# IDP5.net
KiCad netlist of a schematic drawn in EAGLE
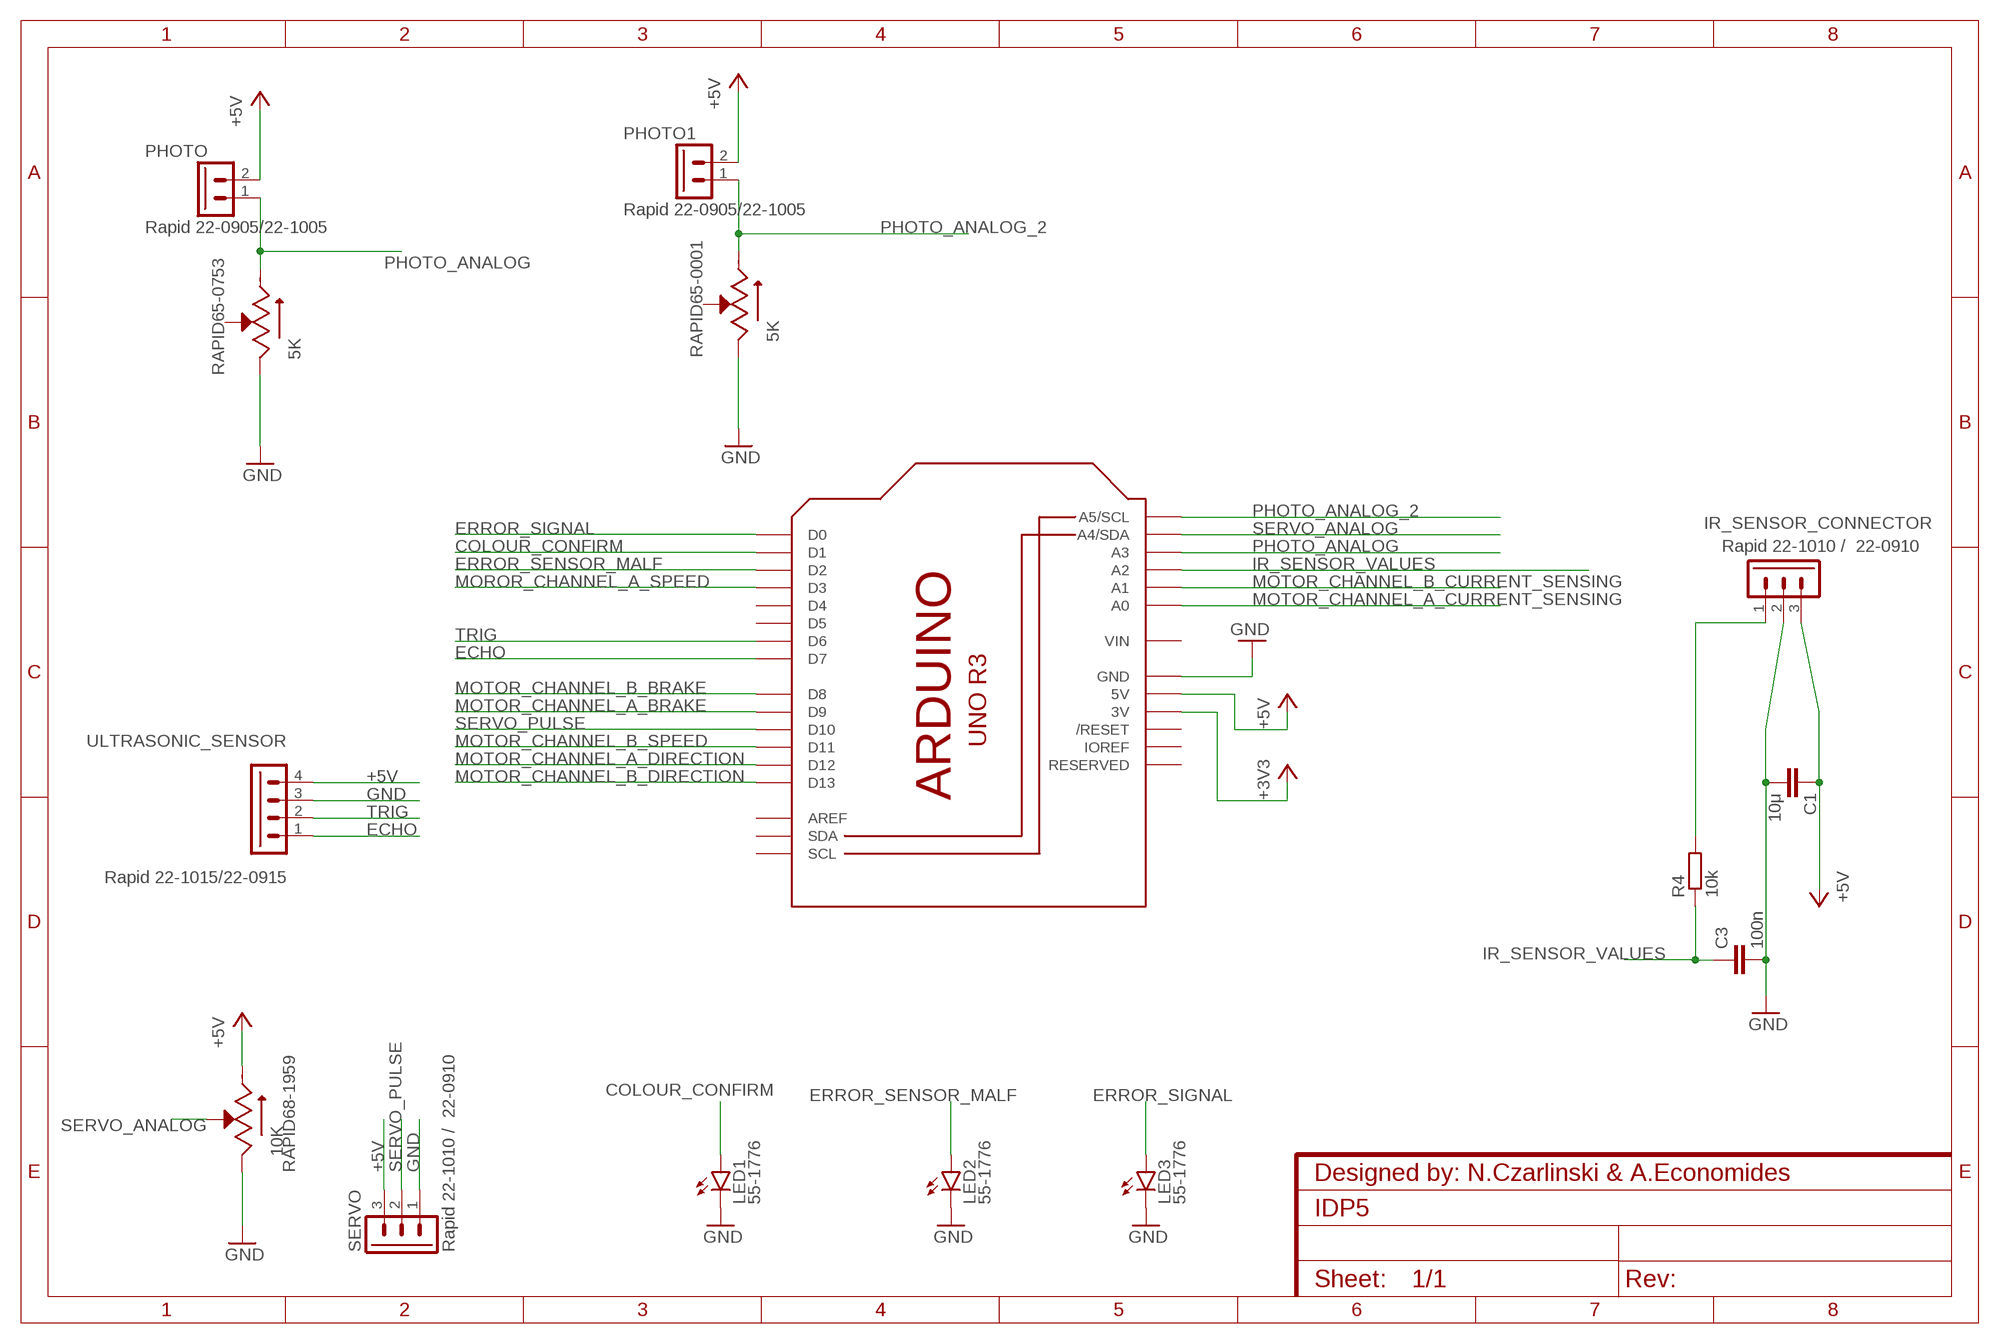
[diagram p0: schematic, sheet 1]

(export (version "E")
  (design (tool "Eeschema 10.0.6"))
  (components
    (comp (ref "C1")
      (value "10μ")
      (footprint "eagle-import:C025-024X044")
      (libsource (lib "eagle-import") (part "C-EU025-024X044"))
    )
    (comp (ref "C3")
      (value "100n")
      (footprint "eagle-import:C025-024X044")
      (libsource (lib "eagle-import") (part "C-EU025-024X044"))
    )
    (comp (ref "IR_SENSOR_CONNECTOR")
      (value "Rapid 22-1010 / 22-0910")
      (footprint "eagle-import:7395-03")
      (fields (field (name "MF") "MOLEX"))
      (libsource (lib "eagle-import") (part "22-?-0305-7038"))
    )
    (comp (ref "LED1")
      (value "55-1776")
      (footprint "eagle-import:LED3MM")
      (libsource (lib "eagle-import") (part "LED_23MM"))
    )
    (comp (ref "LED2")
      (value "55-1776")
      (footprint "eagle-import:LED3MM")
      (libsource (lib "eagle-import") (part "LED_23MM"))
    )
    (comp (ref "LED3")
      (value "55-1776")
      (footprint "eagle-import:LED3MM")
      (libsource (lib "eagle-import") (part "LED_23MM"))
    )
    (comp (ref "M1")
      (value "IDP_PROTOBOARD")
      (footprint "eagle-import:IDP_PROTO")
      (libsource (lib "eagle-import") (part "IDP_PROTOBOARD"))
    )
    (comp (ref "PHOTO")
      (value "Rapid 22-0905/22-1005")
      (footprint "eagle-import:7395-02")
      (fields (field (name "MF") "MOLEX"))
      (libsource (lib "eagle-import") (part "22-?-0205-7028"))
    )
    (comp (ref "PHOTO1")
      (value "Rapid 22-0905/22-1005")
      (footprint "eagle-import:7395-02")
      (fields (field (name "MF") "MOLEX"))
      (libsource (lib "eagle-import") (part "22-?-0205-7028"))
    )
    (comp (ref "R4")
      (value "10k")
      (footprint "eagle-import:0204_7")
      (libsource (lib "eagle-import") (part "R-EU_0204/7"))
    )
    (comp (ref "RAPID65-0001")
      (value "5K")
      (footprint "eagle-import:TRIM_3296W-1-250")
      (fields (field (name "MF") "Bourns") (field (name "MP") "3296W-1-250"))
      (libsource (lib "eagle-import") (part "POT"))
    )
    (comp (ref "RAPID65-0753")
      (value "5K")
      (footprint "eagle-import:TRIM_3296W-1-250")
      (fields (field (name "MF") "Bourns") (field (name "MP") "3296W-1-250"))
      (libsource (lib "eagle-import") (part "POT"))
    )
    (comp (ref "RAPID68-1959")
      (value "10K")
      (footprint "eagle-import:TRIM_3296W-1-250")
      (fields (field (name "MF") "Bourns") (field (name "MP") "3296W-1-250"))
      (libsource (lib "eagle-import") (part "POT"))
    )
    (comp (ref "SERVO")
      (value "Rapid 22-1010 / 22-0910")
      (footprint "eagle-import:7395-03")
      (fields (field (name "MF") "MOLEX"))
      (libsource (lib "eagle-import") (part "22-?-0305-7038"))
    )
    (comp (ref "ULTRASONIC_SENSOR")
      (value "Rapid 22-1015/22-0915")
      (footprint "eagle-import:7395-04")
      (fields (field (name "MF") "MOLEX"))
      (libsource (lib "eagle-import") (part "22-?-0405-7048"))
    )
  )
  (nets
    (net (code "1") (name "+3V3") (class "Default")
      (node (ref "M1") (pin "3V") (pinfunction "3V_3V") (pintype "power_in"))
    )
    (net (code "2") (name "+5V") (class "Default")
      (node (ref "C1") (pin "1") (pinfunction "1_1") (pintype "passive"))
      (node (ref "IR_SENSOR_CONNECTOR") (pin "3") (pinfunction "3_3") (pintype "passive"))
      (node (ref "M1") (pin "5V") (pinfunction "5V_5V") (pintype "power_in"))
      (node (ref "M1") (pin "5V@0") (pinfunction "5V_5V@0") (pintype "power_in"))
      (node (ref "M1") (pin "5V@1") (pinfunction "5V_5V@1") (pintype "power_in"))
      (node (ref "M1") (pin "5V@10") (pinfunction "5V_5V@10") (pintype "power_in"))
      (node (ref "M1") (pin "5V@11") (pinfunction "5V_5V@11") (pintype "power_in"))
      (node (ref "M1") (pin "5V@12") (pinfunction "5V_5V@12") (pintype "power_in"))
      (node (ref "M1") (pin "5V@13") (pinfunction "5V_5V@13") (pintype "power_in"))
      (node (ref "M1") (pin "5V@14") (pinfunction "5V_5V@14") (pintype "power_in"))
      (node (ref "M1") (pin "5V@15") (pinfunction "5V_5V@15") (pintype "power_in"))
      (node (ref "M1") (pin "5V@16") (pinfunction "5V_5V@16") (pintype "power_in"))
      (node (ref "M1") (pin "5V@17") (pinfunction "5V_5V@17") (pintype "power_in"))
      (node (ref "M1") (pin "5V@18") (pinfunction "5V_5V@18") (pintype "power_in"))
      (node (ref "M1") (pin "5V@19") (pinfunction "5V_5V@19") (pintype "power_in"))
      (node (ref "M1") (pin "5V@2") (pinfunction "5V_5V@2") (pintype "power_in"))
      (node (ref "M1") (pin "5V@20") (pinfunction "5V_5V@20") (pintype "power_in"))
      (node (ref "M1") (pin "5V@21") (pinfunction "5V_5V@21") (pintype "power_in"))
      (node (ref "M1") (pin "5V@22") (pinfunction "5V_5V@22") (pintype "power_in"))
      (node (ref "M1") (pin "5V@23") (pinfunction "5V_5V@23") (pintype "power_in"))
      (node (ref "M1") (pin "5V@24") (pinfunction "5V_5V@24") (pintype "power_in"))
      (node (ref "M1") (pin "5V@25") (pinfunction "5V_5V@25") (pintype "power_in"))
      (node (ref "M1") (pin "5V@26") (pinfunction "5V_5V@26") (pintype "power_in"))
      (node (ref "M1") (pin "5V@27") (pinfunction "5V_5V@27") (pintype "power_in"))
      (node (ref "M1") (pin "5V@28") (pinfunction "5V_5V@28") (pintype "power_in"))
      (node (ref "M1") (pin "5V@29") (pinfunction "5V_5V@29") (pintype "power_in"))
      (node (ref "M1") (pin "5V@3") (pinfunction "5V_5V@3") (pintype "power_in"))
      (node (ref "M1") (pin "5V@30") (pinfunction "5V_5V@30") (pintype "power_in"))
      (node (ref "M1") (pin "5V@31") (pinfunction "5V_5V@31") (pintype "power_in"))
      (node (ref "M1") (pin "5V@32") (pinfunction "5V_5V@32") (pintype "power_in"))
      (node (ref "M1") (pin "5V@33") (pinfunction "5V_5V@33") (pintype "power_in"))
      (node (ref "M1") (pin "5V@34") (pinfunction "5V_5V@34") (pintype "power_in"))
      (node (ref "M1") (pin "5V@35") (pinfunction "5V_5V@35") (pintype "power_in"))
      (node (ref "M1") (pin "5V@36") (pinfunction "5V_5V@36") (pintype "power_in"))
      (node (ref "M1") (pin "5V@37") (pinfunction "5V_5V@37") (pintype "power_in"))
      (node (ref "M1") (pin "5V@38") (pinfunction "5V_5V@38") (pintype "power_in"))
      (node (ref "M1") (pin "5V@39") (pinfunction "5V_5V@39") (pintype "power_in"))
      (node (ref "M1") (pin "5V@4") (pinfunction "5V_5V@4") (pintype "power_in"))
      (node (ref "M1") (pin "5V@40") (pinfunction "5V_5V@40") (pintype "power_in"))
      (node (ref "M1") (pin "5V@5") (pinfunction "5V_5V@5") (pintype "power_in"))
      (node (ref "M1") (pin "5V@6") (pinfunction "5V_5V@6") (pintype "power_in"))
      (node (ref "M1") (pin "5V@7") (pinfunction "5V_5V@7") (pintype "power_in"))
      (node (ref "M1") (pin "5V@8") (pinfunction "5V_5V@8") (pintype "power_in"))
      (node (ref "M1") (pin "5V@9") (pinfunction "5V_5V@9") (pintype "power_in"))
      (node (ref "PHOTO") (pin "2") (pinfunction "2_2") (pintype "passive"))
      (node (ref "PHOTO1") (pin "2") (pinfunction "2_2") (pintype "passive"))
      (node (ref "RAPID68-1959") (pin "3") (pinfunction "CW_3") (pintype "passive"))
      (node (ref "SERVO") (pin "3") (pinfunction "3_3") (pintype "passive"))
      (node (ref "ULTRASONIC_SENSOR") (pin "4") (pinfunction "4_4") (pintype "passive"))
    )
    (net (code "3") (name "/COLOUR_CONFIRM") (class "Default")
      (node (ref "LED1") (pin "A") (pinfunction "A_A") (pintype "passive"))
      (node (ref "M1") (pin "D1") (pinfunction "D1_D1") (pintype "bidirectional"))
    )
    (net (code "4") (name "/ECHO") (class "Default")
      (node (ref "M1") (pin "D7") (pinfunction "D7_D7") (pintype "bidirectional"))
      (node (ref "ULTRASONIC_SENSOR") (pin "1") (pinfunction "1_1") (pintype "passive"))
    )
    (net (code "5") (name "/ERROR_SENSOR_MALF") (class "Default")
      (node (ref "LED2") (pin "A") (pinfunction "A_A") (pintype "passive"))
      (node (ref "M1") (pin "D2") (pinfunction "D2_D2") (pintype "bidirectional"))
    )
    (net (code "6") (name "/ERROR_SIGNAL") (class "Default")
      (node (ref "LED3") (pin "A") (pinfunction "A_A") (pintype "passive"))
      (node (ref "M1") (pin "D0") (pinfunction "D0_D0") (pintype "bidirectional"))
    )
    (net (code "7") (name "/IR_SENSOR_VALUES") (class "Default")
      (node (ref "C3") (pin "1") (pinfunction "1_1") (pintype "passive"))
      (node (ref "M1") (pin "A2") (pinfunction "A2_A2") (pintype "bidirectional"))
      (node (ref "R4") (pin "1") (pinfunction "1_1") (pintype "passive"))
    )
    (net (code "8") (name "/MOROR_CHANNEL_A_SPEED") (class "Default")
      (node (ref "M1") (pin "D3") (pinfunction "D3_D3") (pintype "bidirectional"))
    )
    (net (code "9") (name "/MOTOR_CHANNEL_A_BRAKE") (class "Default")
      (node (ref "M1") (pin "D9") (pinfunction "D9_D9") (pintype "bidirectional"))
    )
    (net (code "10") (name "/MOTOR_CHANNEL_A_CURRENT_SENSING") (class "Default")
      (node (ref "M1") (pin "A0") (pinfunction "A0_A0") (pintype "bidirectional"))
    )
    (net (code "11") (name "/MOTOR_CHANNEL_A_DIRECTION") (class "Default")
      (node (ref "M1") (pin "D12") (pinfunction "D12_D12") (pintype "bidirectional"))
    )
    (net (code "12") (name "/MOTOR_CHANNEL_B_BRAKE") (class "Default")
      (node (ref "M1") (pin "D8") (pinfunction "D8_D8") (pintype "bidirectional"))
    )
    (net (code "13") (name "/MOTOR_CHANNEL_B_CURRENT_SENSING") (class "Default")
      (node (ref "M1") (pin "A1") (pinfunction "A1_A1") (pintype "bidirectional"))
    )
    (net (code "14") (name "/MOTOR_CHANNEL_B_DIRECTION") (class "Default")
      (node (ref "M1") (pin "D13") (pinfunction "D13_D13") (pintype "bidirectional"))
    )
    (net (code "15") (name "/MOTOR_CHANNEL_B_SPEED") (class "Default")
      (node (ref "M1") (pin "D11") (pinfunction "D11_D11") (pintype "bidirectional"))
    )
    (net (code "16") (name "/PHOTO_ANALOG") (class "Default")
      (node (ref "M1") (pin "A3") (pinfunction "A3_A3") (pintype "bidirectional"))
      (node (ref "PHOTO") (pin "1") (pinfunction "1_1") (pintype "passive"))
      (node (ref "RAPID65-0753") (pin "3") (pinfunction "CW_3") (pintype "passive"))
    )
    (net (code "17") (name "/PHOTO_ANALOG_2") (class "Default")
      (node (ref "M1") (pin "A5") (pinfunction "A5/SCL_A5") (pintype "bidirectional"))
      (node (ref "PHOTO1") (pin "1") (pinfunction "1_1") (pintype "passive"))
      (node (ref "RAPID65-0001") (pin "3") (pinfunction "CW_3") (pintype "passive"))
    )
    (net (code "18") (name "/SERVO_ANALOG") (class "Default")
      (node (ref "M1") (pin "A4") (pinfunction "A4/SDA_A4") (pintype "bidirectional"))
      (node (ref "RAPID68-1959") (pin "2") (pinfunction "WIPER_2") (pintype "passive"))
    )
    (net (code "19") (name "/SERVO_PULSE") (class "Default")
      (node (ref "M1") (pin "D10") (pinfunction "D10_D10") (pintype "bidirectional"))
      (node (ref "SERVO") (pin "2") (pinfunction "2_2") (pintype "passive"))
    )
    (net (code "20") (name "/TRIG") (class "Default")
      (node (ref "M1") (pin "D6") (pinfunction "D6_D6") (pintype "bidirectional"))
      (node (ref "ULTRASONIC_SENSOR") (pin "2") (pinfunction "2_2") (pintype "passive"))
    )
    (net (code "21") (name "GND") (class "Default")
      (node (ref "C1") (pin "2") (pinfunction "2_2") (pintype "passive"))
      (node (ref "C3") (pin "2") (pinfunction "2_2") (pintype "passive"))
      (node (ref "IR_SENSOR_CONNECTOR") (pin "2") (pinfunction "2_2") (pintype "passive"))
      (node (ref "LED1") (pin "K") (pinfunction "C_K") (pintype "passive"))
      (node (ref "LED2") (pin "K") (pinfunction "C_K") (pintype "passive"))
      (node (ref "LED3") (pin "K") (pinfunction "C_K") (pintype "passive"))
      (node (ref "M1") (pin "GND") (pinfunction "GND_GND") (pintype "power_in"))
      (node (ref "M1") (pin "GND16") (pinfunction "GND_GND16") (pintype "power_in"))
      (node (ref "M1") (pin "GND17") (pinfunction "GND_GND17") (pintype "power_in"))
      (node (ref "M1") (pin "GND18") (pinfunction "GND_GND18") (pintype "power_in"))
      (node (ref "M1") (pin "GND19") (pinfunction "GND_GND19") (pintype "power_in"))
      (node (ref "M1") (pin "GND20") (pinfunction "GND_GND20") (pintype "power_in"))
      (node (ref "M1") (pin "GND21") (pinfunction "GND_GND21") (pintype "power_in"))
      (node (ref "M1") (pin "GND22") (pinfunction "GND_GND22") (pintype "power_in"))
      (node (ref "M1") (pin "GND23") (pinfunction "GND_GND23") (pintype "power_in"))
      (node (ref "M1") (pin "GND24") (pinfunction "GND_GND24") (pintype "power_in"))
      (node (ref "M1") (pin "GND25") (pinfunction "GND_GND25") (pintype "power_in"))
      (node (ref "M1") (pin "GND@1") (pinfunction "GND_GND@1") (pintype "power_in"))
      (node (ref "M1") (pin "GND@10") (pinfunction "GND_GND@10") (pintype "power_in"))
      (node (ref "M1") (pin "GND@11") (pinfunction "GND_GND@11") (pintype "power_in"))
      (node (ref "M1") (pin "GND@12") (pinfunction "GND_GND@12") (pintype "power_in"))
      (node (ref "M1") (pin "GND@13") (pinfunction "GND_GND@13") (pintype "power_in"))
      (node (ref "M1") (pin "GND@14") (pinfunction "GND_GND@14") (pintype "power_in"))
      (node (ref "M1") (pin "GND@15") (pinfunction "GND_GND@15") (pintype "power_in"))
      (node (ref "M1") (pin "GND@2") (pinfunction "GND_GND@2") (pintype "power_in"))
      (node (ref "M1") (pin "GND@26") (pinfunction "GND_GND@26") (pintype "power_in"))
      (node (ref "M1") (pin "GND@27") (pinfunction "GND_GND@27") (pintype "power_in"))
      (node (ref "M1") (pin "GND@28") (pinfunction "GND_GND@28") (pintype "power_in"))
      (node (ref "M1") (pin "GND@29") (pinfunction "GND_GND@29") (pintype "power_in"))
      (node (ref "M1") (pin "GND@3") (pinfunction "GND_GND@3") (pintype "power_in"))
      (node (ref "M1") (pin "GND@30") (pinfunction "GND_GND@30") (pintype "power_in"))
      (node (ref "M1") (pin "GND@31") (pinfunction "GND_GND@31") (pintype "power_in"))
      (node (ref "M1") (pin "GND@32") (pinfunction "GND_GND@32") (pintype "power_in"))
      (node (ref "M1") (pin "GND@33") (pinfunction "GND_GND@33") (pintype "power_in"))
      (node (ref "M1") (pin "GND@34") (pinfunction "GND_GND@34") (pintype "power_in"))
      (node (ref "M1") (pin "GND@35") (pinfunction "GND_GND@35") (pintype "power_in"))
      (node (ref "M1") (pin "GND@36") (pinfunction "GND_GND@36") (pintype "power_in"))
      (node (ref "M1") (pin "GND@37") (pinfunction "GND_GND@37") (pintype "power_in"))
      (node (ref "M1") (pin "GND@38") (pinfunction "GND_GND@38") (pintype "power_in"))
      (node (ref "M1") (pin "GND@39") (pinfunction "GND_GND@39") (pintype "power_in"))
      (node (ref "M1") (pin "GND@4") (pinfunction "GND_GND@4") (pintype "power_in"))
      (node (ref "M1") (pin "GND@40") (pinfunction "GND_GND@40") (pintype "power_in"))
      (node (ref "M1") (pin "GND@41") (pinfunction "GND_GND@41") (pintype "power_in"))
      (node (ref "M1") (pin "GND@42") (pinfunction "GND_GND@42") (pintype "power_in"))
      (node (ref "M1") (pin "GND@43") (pinfunction "GND_GND@43") (pintype "power_in"))
      (node (ref "M1") (pin "GND@44") (pinfunction "GND_GND@44") (pintype "power_in"))
      (node (ref "M1") (pin "GND@45") (pinfunction "GND_GND@45") (pintype "power_in"))
      (node (ref "M1") (pin "GND@46") (pinfunction "GND_GND@46") (pintype "power_in"))
      (node (ref "M1") (pin "GND@47") (pinfunction "GND_GND@47") (pintype "power_in"))
      (node (ref "M1") (pin "GND@48") (pinfunction "GND_GND@48") (pintype "power_in"))
      (node (ref "M1") (pin "GND@5") (pinfunction "GND_GND@5") (pintype "power_in"))
      (node (ref "M1") (pin "GND@6") (pinfunction "GND_GND@6") (pintype "power_in"))
      (node (ref "M1") (pin "GND@7") (pinfunction "GND_GND@7") (pintype "power_in"))
      (node (ref "M1") (pin "GND@8") (pinfunction "GND_GND@8") (pintype "power_in"))
      (node (ref "M1") (pin "GND@9") (pinfunction "GND_GND@9") (pintype "power_in"))
      (node (ref "RAPID65-0001") (pin "1") (pinfunction "CCW_1") (pintype "passive"))
      (node (ref "RAPID65-0753") (pin "1") (pinfunction "CCW_1") (pintype "passive"))
      (node (ref "RAPID68-1959") (pin "1") (pinfunction "CCW_1") (pintype "passive"))
      (node (ref "SERVO") (pin "1") (pinfunction "1_1") (pintype "passive"))
      (node (ref "ULTRASONIC_SENSOR") (pin "3") (pinfunction "3_3") (pintype "passive"))
    )
    (net (code "22") (name "Net-(IR_SENSOR_CONNECTOR-Pad1)") (class "Default")
      (node (ref "IR_SENSOR_CONNECTOR") (pin "1") (pinfunction "1_1") (pintype "passive"))
      (node (ref "R4") (pin "2") (pinfunction "2_2") (pintype "passive"))
    )
    (net (code "23") (name "unconnected-(M1-PadAREF)") (class "Default")
      (node (ref "M1") (pin "AREF") (pinfunction "AREF_AREF") (pintype "bidirectional"))
    )
    (net (code "24") (name "unconnected-(M1-PadD4)") (class "Default")
      (node (ref "M1") (pin "D4") (pinfunction "D4_D4") (pintype "bidirectional"))
    )
    (net (code "25") (name "unconnected-(M1-PadD5)") (class "Default")
      (node (ref "M1") (pin "D5") (pinfunction "D5_D5") (pintype "bidirectional"))
    )
    (net (code "26") (name "unconnected-(M1-PadIOREF)") (class "Default")
      (node (ref "M1") (pin "IOREF") (pinfunction "IOREF_IOREF") (pintype "output"))
    )
    (net (code "27") (name "unconnected-(M1-PadRESERVED)") (class "Default")
      (node (ref "M1") (pin "RESERVED") (pinfunction "RESERVED_RESERVED") (pintype "no_connect"))
    )
    (net (code "28") (name "unconnected-(M1-PadSCL)") (class "Default")
      (node (ref "M1") (pin "SCL") (pinfunction "SCL_SCL") (pintype "bidirectional"))
    )
    (net (code "29") (name "unconnected-(M1-PadSDA)") (class "Default")
      (node (ref "M1") (pin "SDA") (pinfunction "SDA_SDA") (pintype "bidirectional"))
    )
    (net (code "30") (name "unconnected-(M1-PadVIN)") (class "Default")
      (node (ref "M1") (pin "VIN") (pinfunction "VIN_VIN") (pintype "no_connect"))
    )
    (net (code "31") (name "unconnected-(M1-{slash}RESET-PadRESET)") (class "Default")
      (node (ref "M1") (pin "RESET") (pinfunction "/RESET_RESET") (pintype "bidirectional"))
    )
    (net (code "32") (name "unconnected-(RAPID65-0001-WIPER-Pad2)") (class "Default")
      (node (ref "RAPID65-0001") (pin "2") (pinfunction "WIPER_2") (pintype "passive"))
    )
    (net (code "33") (name "unconnected-(RAPID65-0753-WIPER-Pad2)") (class "Default")
      (node (ref "RAPID65-0753") (pin "2") (pinfunction "WIPER_2") (pintype "passive"))
    )
  )
)
